# A-2_sch.net
KiCad netlist of a schematic drawn in EAGLE
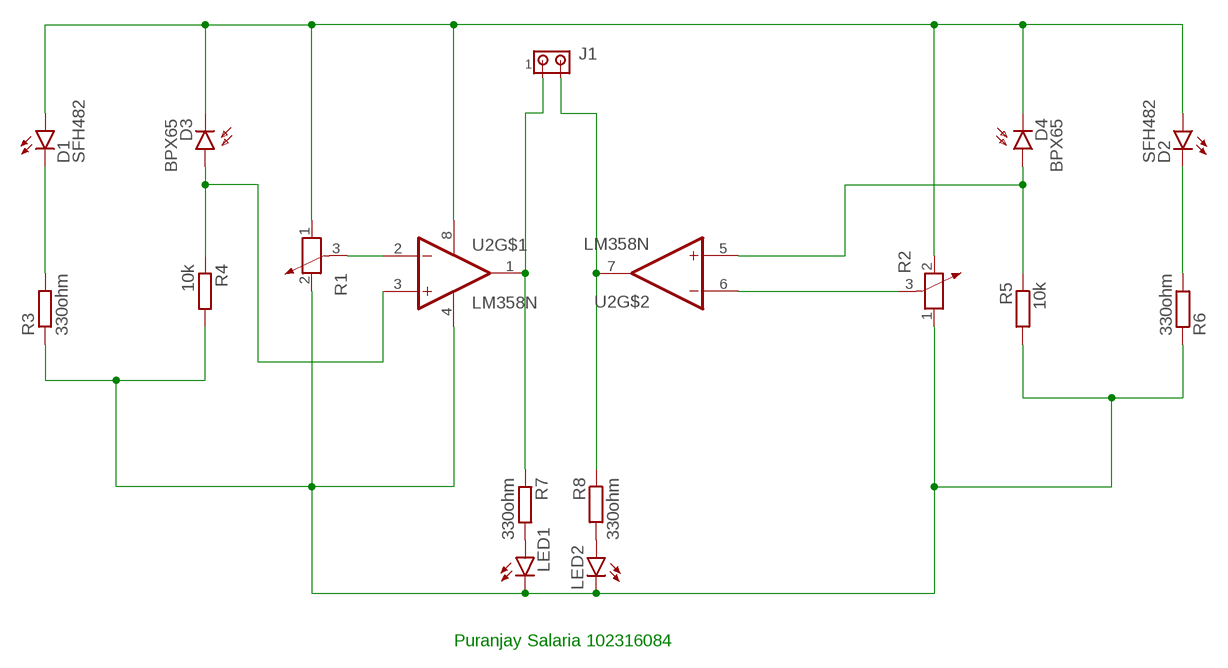
[diagram p0: schematic, sheet 1]

(export (version "E")
  (design (tool "Eeschema 10.0.6"))
  (components
    (comp (ref "D1")
      (value "SFH482")
      (footprint "eagle-import:SFH482")
      (libsource (lib "eagle-import") (part "SFH482"))
    )
    (comp (ref "D2")
      (value "SFH482")
      (footprint "eagle-import:SFH482")
      (libsource (lib "eagle-import") (part "SFH482"))
    )
    (comp (ref "D3")
      (value "BPX65")
      (footprint "eagle-import:BPX65")
      (fields (field (name "MPN") "BPX65."))
      (libsource (lib "eagle-import") (part "BPX65"))
    )
    (comp (ref "D4")
      (value "BPX65")
      (footprint "eagle-import:BPX65")
      (fields (field (name "MPN") "BPX65."))
      (libsource (lib "eagle-import") (part "BPX65"))
    )
    (comp (ref "J1")
      (value "MTA02-100")
      (footprint "eagle-import:10X02MTA")
      (libsource (lib "eagle-import") (part "MTA02-100"))
    )
    (comp (ref "LED1")
      (value "LED3MM")
      (footprint "eagle-import:LED3MM")
      (libsource (lib "eagle-import") (part "LED3MM"))
    )
    (comp (ref "LED2")
      (value "LED3MM")
      (footprint "eagle-import:LED3MM")
      (libsource (lib "eagle-import") (part "LED3MM"))
    )
    (comp (ref "R1")
      (value "POTENTIOMETER_PT-10")
      (footprint "eagle-import:PT-10")
      (libsource (lib "eagle-import") (part "POTENTIOMETER_PT-10"))
    )
    (comp (ref "R2")
      (value "POTENTIOMETER_PT-10")
      (footprint "eagle-import:PT-10")
      (libsource (lib "eagle-import") (part "POTENTIOMETER_PT-10"))
    )
    (comp (ref "R3")
      (value "330ohm")
      (footprint "eagle-import:0204_5")
      (libsource (lib "eagle-import") (part "R-EU_0204/5"))
    )
    (comp (ref "R4")
      (value "10k")
      (footprint "eagle-import:0204_5")
      (libsource (lib "eagle-import") (part "R-EU_0204/5"))
    )
    (comp (ref "R5")
      (value "10k")
      (footprint "eagle-import:0204_5")
      (libsource (lib "eagle-import") (part "R-EU_0204/5"))
    )
    (comp (ref "R6")
      (value "330ohm")
      (footprint "eagle-import:0204_5")
      (libsource (lib "eagle-import") (part "R-EU_0204/5"))
    )
    (comp (ref "R7")
      (value "330ohm")
      (footprint "eagle-import:0204_5")
      (libsource (lib "eagle-import") (part "R-EU_0204/5"))
    )
    (comp (ref "R8")
      (value "330ohm")
      (footprint "eagle-import:0204_5")
      (libsource (lib "eagle-import") (part "R-EU_0204/5"))
    )
    (comp (ref "U2")
      (value "LM358N")
      (footprint "eagle-import:DIP762W46P254L960H508Q8")
      (fields (field (name "MF") "Harris Corporation"))
      (libsource (lib "eagle-import") (part "LM358N"))
    )
  )
  (nets
    (net (code "1") (name "Net-(D1-C)") (class "Default")
      (node (ref "D1") (pin "K") (pinfunction "C_K") (pintype "passive"))
      (node (ref "R3") (pin "2") (pinfunction "2_2") (pintype "passive"))
    )
    (net (code "2") (name "Net-(D2-C)") (class "Default")
      (node (ref "D2") (pin "K") (pinfunction "C_K") (pintype "passive"))
      (node (ref "R6") (pin "2") (pinfunction "2_2") (pintype "passive"))
    )
    (net (code "3") (name "Net-(D3-C)") (class "Default")
      (node (ref "D1") (pin "A") (pinfunction "A_A") (pintype "passive"))
      (node (ref "D2") (pin "A") (pinfunction "A_A") (pintype "passive"))
      (node (ref "D3") (pin "K") (pinfunction "C_K") (pintype "passive"))
      (node (ref "D4") (pin "K") (pinfunction "C_K") (pintype "passive"))
      (node (ref "R1") (pin "1") (pinfunction "1_1") (pintype "passive"))
      (node (ref "R2") (pin "2") (pinfunction "2_2") (pintype "passive"))
      (node (ref "U2") (pin "8") (pinfunction "VCC_8") (pintype "power_in"))
    )
    (net (code "4") (name "Net-(LED1-C)") (class "Default")
      (node (ref "LED1") (pin "K") (pinfunction "C_K") (pintype "passive"))
      (node (ref "LED2") (pin "K") (pinfunction "C_K") (pintype "passive"))
      (node (ref "R1") (pin "2") (pinfunction "2_2") (pintype "passive"))
      (node (ref "R2") (pin "1") (pinfunction "1_1") (pintype "passive"))
      (node (ref "R3") (pin "1") (pinfunction "1_1") (pintype "passive"))
      (node (ref "R4") (pin "2") (pinfunction "2_2") (pintype "passive"))
      (node (ref "R5") (pin "2") (pinfunction "2_2") (pintype "passive"))
      (node (ref "R6") (pin "1") (pinfunction "1_1") (pintype "passive"))
      (node (ref "U2") (pin "4") (pinfunction "GND_4") (pintype "power_in"))
    )
    (net (code "5") (name "Net-(LED1-PadA)") (class "Default")
      (node (ref "LED1") (pin "A") (pinfunction "A_A") (pintype "passive"))
      (node (ref "R7") (pin "2") (pinfunction "2_2") (pintype "passive"))
    )
    (net (code "6") (name "Net-(LED2-PadA)") (class "Default")
      (node (ref "LED2") (pin "A") (pinfunction "A_A") (pintype "passive"))
      (node (ref "R8") (pin "2") (pinfunction "2_2") (pintype "passive"))
    )
    (net (code "7") (name "Net-(U2A-1IN+)") (class "Default")
      (node (ref "D3") (pin "A") (pinfunction "A_A") (pintype "passive"))
      (node (ref "R4") (pin "1") (pinfunction "1_1") (pintype "passive"))
      (node (ref "U2") (pin "3") (pinfunction "1IN+_3") (pintype "input"))
    )
    (net (code "8") (name "Net-(U2A-1IN-)") (class "Default")
      (node (ref "R1") (pin "3") (pinfunction "3_3") (pintype "passive"))
      (node (ref "U2") (pin "2") (pinfunction "1IN-_2") (pintype "input"))
    )
    (net (code "9") (name "Net-(U2A-1OUT)") (class "Default")
      (node (ref "J1") (pin "1") (pinfunction "1_1") (pintype "passive"))
      (node (ref "R7") (pin "1") (pinfunction "1_1") (pintype "passive"))
      (node (ref "U2") (pin "1") (pinfunction "1OUT_1") (pintype "output"))
    )
    (net (code "10") (name "Net-(U2B-2IN+)") (class "Default")
      (node (ref "D4") (pin "A") (pinfunction "A_A") (pintype "passive"))
      (node (ref "R5") (pin "1") (pinfunction "1_1") (pintype "passive"))
      (node (ref "U2") (pin "5") (pinfunction "2IN+_5") (pintype "input"))
    )
    (net (code "11") (name "Net-(U2B-2IN-)") (class "Default")
      (node (ref "R2") (pin "3") (pinfunction "3_3") (pintype "passive"))
      (node (ref "U2") (pin "6") (pinfunction "2IN-_6") (pintype "input"))
    )
    (net (code "12") (name "Net-(U2B-2OUT)") (class "Default")
      (node (ref "J1") (pin "2") (pinfunction "2_2") (pintype "passive"))
      (node (ref "R8") (pin "1") (pinfunction "1_1") (pintype "passive"))
      (node (ref "U2") (pin "7") (pinfunction "2OUT_7") (pintype "output"))
    )
  )
)
